# Ponte_h_-_Alternativa_2.net
KiCad netlist of a schematic drawn in EAGLE
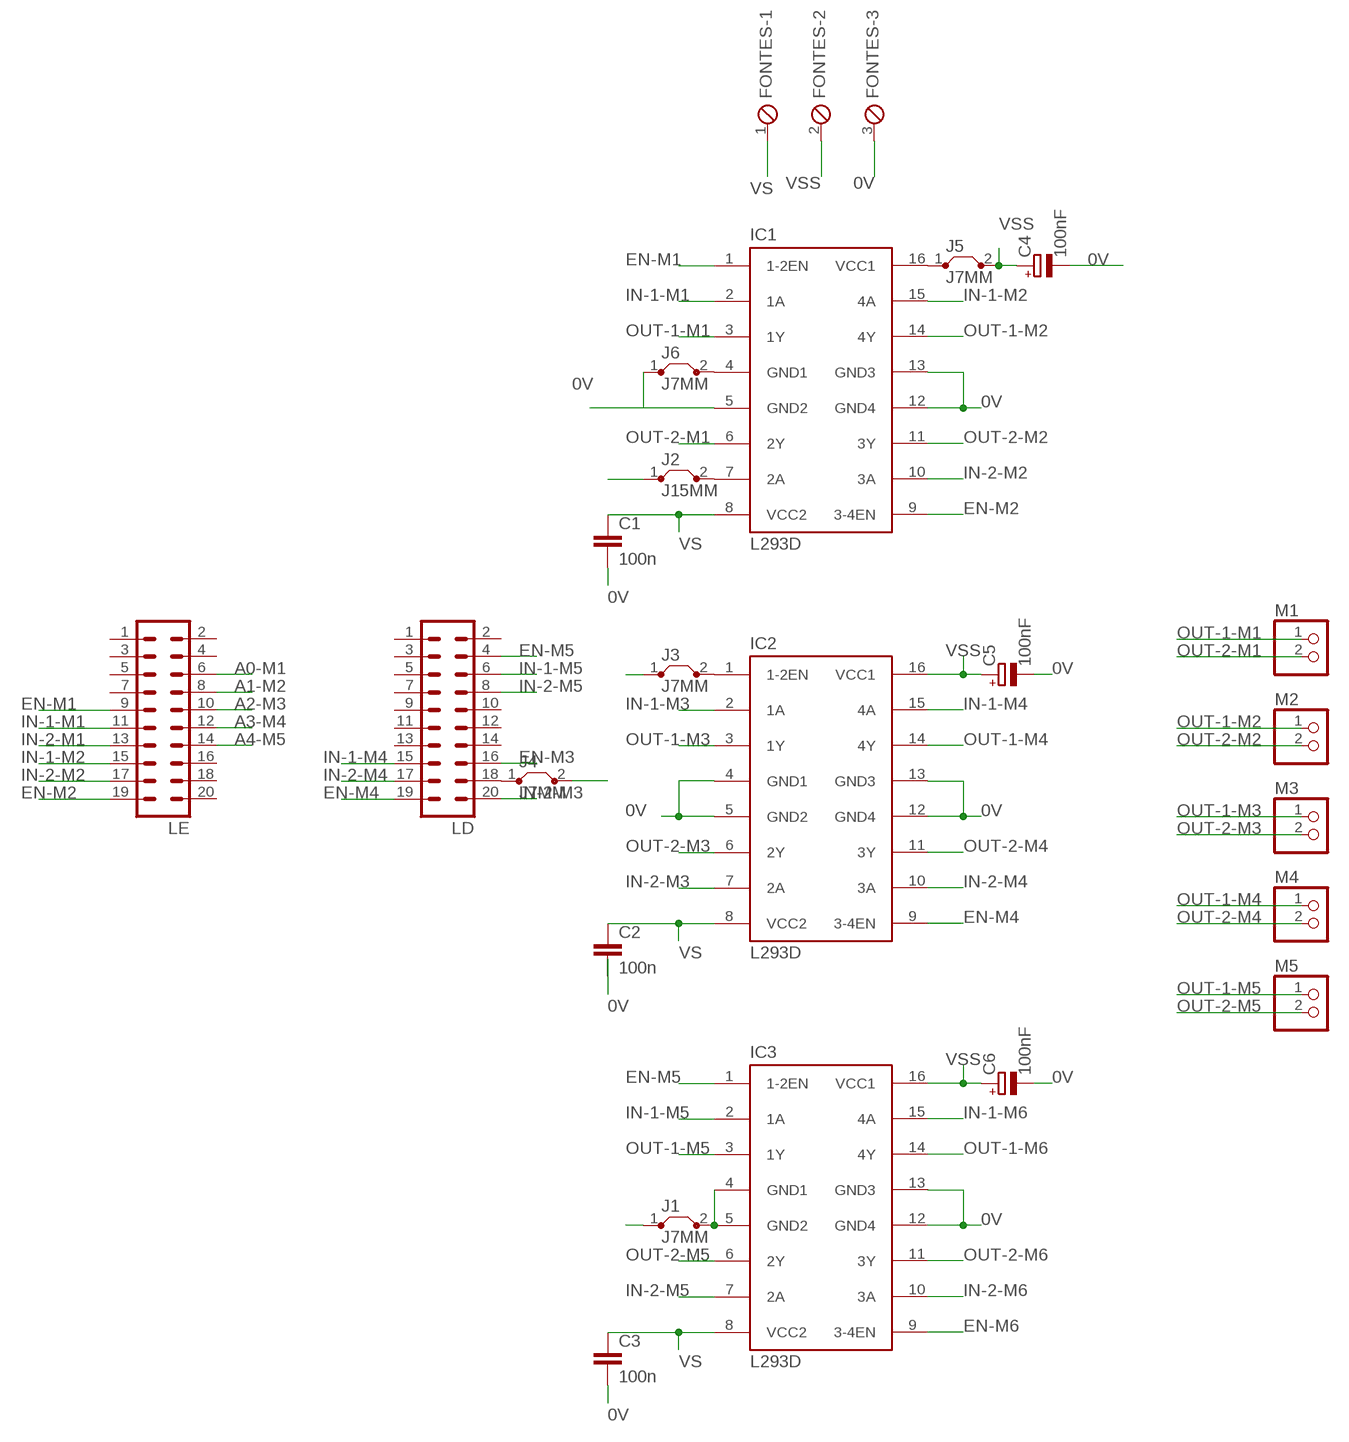
[diagram p0: schematic, sheet 1]

(export (version "E")
  (design (tool "Eeschema 10.0.6"))
  (components
    (comp (ref "C1")
      (value "100n")
      (footprint "eagle-import:C7.5B3")
      (libsource (lib "eagle-import") (part "C7.5/3"))
    )
    (comp (ref "C2")
      (value "100n")
      (footprint "eagle-import:C7.5B3")
      (libsource (lib "eagle-import") (part "C7.5/3"))
    )
    (comp (ref "C3")
      (value "100n")
      (footprint "eagle-import:C7.5B3")
      (libsource (lib "eagle-import") (part "C7.5/3"))
    )
    (comp (ref "C4")
      (value "100nF")
      (footprint "eagle-import:E1,8-4")
      (libsource (lib "eagle-import") (part "CPOL-EUE1.8-4"))
    )
    (comp (ref "C5")
      (value "100nF")
      (footprint "eagle-import:E1,8-4")
      (libsource (lib "eagle-import") (part "CPOL-EUE1.8-4"))
    )
    (comp (ref "C6")
      (value "100nF")
      (footprint "eagle-import:E1,8-4")
      (libsource (lib "eagle-import") (part "CPOL-EUE1.8-4"))
    )
    (comp (ref "FONTES")
      (value "MPT3")
      (footprint "eagle-import:3POL254")
      (libsource (lib "eagle-import") (part "MPT3"))
    )
    (comp (ref "IC1")
      (value "L293D")
      (footprint "eagle-import:DIL16")
      (libsource (lib "eagle-import") (part "L293D"))
    )
    (comp (ref "IC2")
      (value "L293D")
      (footprint "eagle-import:DIL16")
      (libsource (lib "eagle-import") (part "L293D"))
    )
    (comp (ref "IC3")
      (value "L293D")
      (footprint "eagle-import:DIL16")
      (libsource (lib "eagle-import") (part "L293D"))
    )
    (comp (ref "J1")
      (value "J7MM")
      (footprint "eagle-import:07")
      (libsource (lib "eagle-import") (part "J7MM"))
    )
    (comp (ref "J2")
      (value "J15MM")
      (footprint "eagle-import:15")
      (libsource (lib "eagle-import") (part "J15MM"))
    )
    (comp (ref "J3")
      (value "J7MM")
      (footprint "eagle-import:07")
      (libsource (lib "eagle-import") (part "J7MM"))
    )
    (comp (ref "J4")
      (value "J7MM")
      (footprint "eagle-import:07")
      (libsource (lib "eagle-import") (part "J7MM"))
    )
    (comp (ref "J5")
      (value "J7MM")
      (footprint "eagle-import:07")
      (libsource (lib "eagle-import") (part "J7MM"))
    )
    (comp (ref "J6")
      (value "J7MM")
      (footprint "eagle-import:07")
      (libsource (lib "eagle-import") (part "J7MM"))
    )
    (comp (ref "LD")
      (value "MA10-2")
      (footprint "eagle-import:MA10-2")
      (libsource (lib "eagle-import") (part "MA10-2"))
    )
    (comp (ref "LE")
      (value "MA10-2")
      (footprint "eagle-import:MA10-2")
      (libsource (lib "eagle-import") (part "MA10-2"))
    )
    (comp (ref "M1")
      (value "PINHD-1X2")
      (footprint "eagle-import:1X02")
      (libsource (lib "eagle-import") (part "PINHD-1X2"))
    )
    (comp (ref "M2")
      (value "PINHD-1X2")
      (footprint "eagle-import:1X02")
      (libsource (lib "eagle-import") (part "PINHD-1X2"))
    )
    (comp (ref "M3")
      (value "PINHD-1X2")
      (footprint "eagle-import:1X02")
      (libsource (lib "eagle-import") (part "PINHD-1X2"))
    )
    (comp (ref "M4")
      (value "PINHD-1X2")
      (footprint "eagle-import:1X02")
      (libsource (lib "eagle-import") (part "PINHD-1X2"))
    )
    (comp (ref "M5")
      (value "PINHD-1X2")
      (footprint "eagle-import:1X02")
      (libsource (lib "eagle-import") (part "PINHD-1X2"))
    )
  )
  (nets
    (net (code "1") (name "/0V") (class "Default")
      (node (ref "C1") (pin "2") (pinfunction "2_2") (pintype "passive"))
      (node (ref "C2") (pin "2") (pinfunction "2_2") (pintype "passive"))
      (node (ref "C3") (pin "2") (pinfunction "2_2") (pintype "passive"))
      (node (ref "C4") (pin "-") (pinfunction "-_-") (pintype "passive"))
      (node (ref "C5") (pin "-") (pinfunction "-_-") (pintype "passive"))
      (node (ref "C6") (pin "-") (pinfunction "-_-") (pintype "passive"))
      (node (ref "FONTES") (pin "3") (pinfunction "1_3") (pintype "passive"))
      (node (ref "IC1") (pin "12") (pinfunction "GND4_12") (pintype "power_in"))
      (node (ref "IC1") (pin "13") (pinfunction "GND3_13") (pintype "power_in"))
      (node (ref "IC1") (pin "5") (pinfunction "GND2_5") (pintype "power_in"))
      (node (ref "IC2") (pin "12") (pinfunction "GND4_12") (pintype "power_in"))
      (node (ref "IC2") (pin "13") (pinfunction "GND3_13") (pintype "power_in"))
      (node (ref "IC2") (pin "4") (pinfunction "GND1_4") (pintype "power_in"))
      (node (ref "IC2") (pin "5") (pinfunction "GND2_5") (pintype "power_in"))
      (node (ref "IC3") (pin "12") (pinfunction "GND4_12") (pintype "power_in"))
      (node (ref "IC3") (pin "13") (pinfunction "GND3_13") (pintype "power_in"))
      (node (ref "J1") (pin "1") (pinfunction "1_1") (pintype "passive"))
      (node (ref "J6") (pin "1") (pinfunction "1_1") (pintype "passive"))
    )
    (net (code "2") (name "/A0-M1") (class "Default")
      (node (ref "LE") (pin "6") (pinfunction "6_6") (pintype "passive"))
    )
    (net (code "3") (name "/A1-M2") (class "Default")
      (node (ref "LE") (pin "8") (pinfunction "8_8") (pintype "passive"))
    )
    (net (code "4") (name "/A2-M3") (class "Default")
      (node (ref "LE") (pin "10") (pinfunction "10_10") (pintype "passive"))
    )
    (net (code "5") (name "/A3-M4") (class "Default")
      (node (ref "LE") (pin "12") (pinfunction "12_12") (pintype "passive"))
    )
    (net (code "6") (name "/A4-M5") (class "Default")
      (node (ref "LE") (pin "14") (pinfunction "14_14") (pintype "passive"))
    )
    (net (code "7") (name "/EN-M1") (class "Default")
      (node (ref "IC1") (pin "1") (pinfunction "1-2EN_1") (pintype "input"))
      (node (ref "LE") (pin "9") (pinfunction "9_9") (pintype "passive"))
    )
    (net (code "8") (name "/EN-M2") (class "Default")
      (node (ref "IC1") (pin "9") (pinfunction "3-4EN_9") (pintype "input"))
      (node (ref "LE") (pin "19") (pinfunction "19_19") (pintype "passive"))
    )
    (net (code "9") (name "/EN-M3") (class "Default")
      (node (ref "J3") (pin "1") (pinfunction "1_1") (pintype "passive"))
      (node (ref "J4") (pin "2") (pinfunction "2_2") (pintype "passive"))
      (node (ref "LD") (pin "16") (pinfunction "16_16") (pintype "passive"))
    )
    (net (code "10") (name "/EN-M4") (class "Default")
      (node (ref "IC2") (pin "9") (pinfunction "3-4EN_9") (pintype "input"))
      (node (ref "LD") (pin "19") (pinfunction "19_19") (pintype "passive"))
    )
    (net (code "11") (name "/EN-M5") (class "Default")
      (node (ref "IC3") (pin "1") (pinfunction "1-2EN_1") (pintype "input"))
      (node (ref "LD") (pin "4") (pinfunction "4_4") (pintype "passive"))
    )
    (net (code "12") (name "/EN-M6") (class "Default")
      (node (ref "IC3") (pin "9") (pinfunction "3-4EN_9") (pintype "input"))
    )
    (net (code "13") (name "/IN-1-M1") (class "Default")
      (node (ref "IC1") (pin "2") (pinfunction "1A_2") (pintype "input"))
      (node (ref "LE") (pin "11") (pinfunction "11_11") (pintype "passive"))
    )
    (net (code "14") (name "/IN-1-M2") (class "Default")
      (node (ref "IC1") (pin "15") (pinfunction "4A_15") (pintype "input"))
      (node (ref "LE") (pin "15") (pinfunction "15_15") (pintype "passive"))
    )
    (net (code "15") (name "/IN-1-M3") (class "Default")
      (node (ref "IC2") (pin "2") (pinfunction "1A_2") (pintype "input"))
    )
    (net (code "16") (name "/IN-1-M4") (class "Default")
      (node (ref "IC2") (pin "15") (pinfunction "4A_15") (pintype "input"))
      (node (ref "LD") (pin "15") (pinfunction "15_15") (pintype "passive"))
    )
    (net (code "17") (name "/IN-1-M5") (class "Default")
      (node (ref "IC3") (pin "2") (pinfunction "1A_2") (pintype "input"))
      (node (ref "LD") (pin "6") (pinfunction "6_6") (pintype "passive"))
    )
    (net (code "18") (name "/IN-1-M6") (class "Default")
      (node (ref "IC3") (pin "15") (pinfunction "4A_15") (pintype "input"))
    )
    (net (code "19") (name "/IN-2-M1") (class "Default")
      (node (ref "J2") (pin "1") (pinfunction "1_1") (pintype "passive"))
      (node (ref "LE") (pin "13") (pinfunction "13_13") (pintype "passive"))
    )
    (net (code "20") (name "/IN-2-M2") (class "Default")
      (node (ref "IC1") (pin "10") (pinfunction "3A_10") (pintype "input"))
      (node (ref "LE") (pin "17") (pinfunction "17_17") (pintype "passive"))
    )
    (net (code "21") (name "/IN-2-M3") (class "Default")
      (node (ref "IC2") (pin "7") (pinfunction "2A_7") (pintype "input"))
      (node (ref "LD") (pin "20") (pinfunction "20_20") (pintype "passive"))
    )
    (net (code "22") (name "/IN-2-M4") (class "Default")
      (node (ref "IC2") (pin "10") (pinfunction "3A_10") (pintype "input"))
      (node (ref "LD") (pin "17") (pinfunction "17_17") (pintype "passive"))
    )
    (net (code "23") (name "/IN-2-M5") (class "Default")
      (node (ref "IC3") (pin "7") (pinfunction "2A_7") (pintype "input"))
      (node (ref "LD") (pin "8") (pinfunction "8_8") (pintype "passive"))
    )
    (net (code "24") (name "/IN-2-M6") (class "Default")
      (node (ref "IC3") (pin "10") (pinfunction "3A_10") (pintype "input"))
    )
    (net (code "25") (name "/OUT-1-M1") (class "Default")
      (node (ref "IC1") (pin "3") (pinfunction "1Y_3") (pintype "output"))
      (node (ref "M1") (pin "1") (pinfunction "1_1") (pintype "passive"))
    )
    (net (code "26") (name "/OUT-1-M2") (class "Default")
      (node (ref "IC1") (pin "14") (pinfunction "4Y_14") (pintype "output"))
      (node (ref "M2") (pin "1") (pinfunction "1_1") (pintype "passive"))
    )
    (net (code "27") (name "/OUT-1-M3") (class "Default")
      (node (ref "IC2") (pin "3") (pinfunction "1Y_3") (pintype "output"))
      (node (ref "M3") (pin "1") (pinfunction "1_1") (pintype "passive"))
    )
    (net (code "28") (name "/OUT-1-M4") (class "Default")
      (node (ref "IC2") (pin "14") (pinfunction "4Y_14") (pintype "output"))
      (node (ref "M4") (pin "1") (pinfunction "1_1") (pintype "passive"))
    )
    (net (code "29") (name "/OUT-1-M5") (class "Default")
      (node (ref "IC3") (pin "3") (pinfunction "1Y_3") (pintype "output"))
      (node (ref "M5") (pin "1") (pinfunction "1_1") (pintype "passive"))
    )
    (net (code "30") (name "/OUT-1-M6") (class "Default")
      (node (ref "IC3") (pin "14") (pinfunction "4Y_14") (pintype "output"))
    )
    (net (code "31") (name "/OUT-2-M1") (class "Default")
      (node (ref "IC1") (pin "6") (pinfunction "2Y_6") (pintype "output"))
      (node (ref "M1") (pin "2") (pinfunction "2_2") (pintype "passive"))
    )
    (net (code "32") (name "/OUT-2-M2") (class "Default")
      (node (ref "IC1") (pin "11") (pinfunction "3Y_11") (pintype "output"))
      (node (ref "M2") (pin "2") (pinfunction "2_2") (pintype "passive"))
    )
    (net (code "33") (name "/OUT-2-M3") (class "Default")
      (node (ref "IC2") (pin "6") (pinfunction "2Y_6") (pintype "output"))
      (node (ref "M3") (pin "2") (pinfunction "2_2") (pintype "passive"))
    )
    (net (code "34") (name "/OUT-2-M4") (class "Default")
      (node (ref "IC2") (pin "11") (pinfunction "3Y_11") (pintype "output"))
      (node (ref "M4") (pin "2") (pinfunction "2_2") (pintype "passive"))
    )
    (net (code "35") (name "/OUT-2-M5") (class "Default")
      (node (ref "IC3") (pin "6") (pinfunction "2Y_6") (pintype "output"))
      (node (ref "M5") (pin "2") (pinfunction "2_2") (pintype "passive"))
    )
    (net (code "36") (name "/OUT-2-M6") (class "Default")
      (node (ref "IC3") (pin "11") (pinfunction "3Y_11") (pintype "output"))
    )
    (net (code "37") (name "/VS") (class "Default")
      (node (ref "C1") (pin "1") (pinfunction "1_1") (pintype "passive"))
      (node (ref "C2") (pin "1") (pinfunction "1_1") (pintype "passive"))
      (node (ref "C3") (pin "1") (pinfunction "1_1") (pintype "passive"))
      (node (ref "FONTES") (pin "1") (pinfunction "1_1") (pintype "passive"))
      (node (ref "IC1") (pin "8") (pinfunction "VCC2_8") (pintype "power_in"))
      (node (ref "IC2") (pin "8") (pinfunction "VCC2_8") (pintype "power_in"))
      (node (ref "IC3") (pin "8") (pinfunction "VCC2_8") (pintype "power_in"))
    )
    (net (code "38") (name "/VSS") (class "Default")
      (node (ref "C4") (pin "+") (pinfunction "+_+") (pintype "passive"))
      (node (ref "C5") (pin "+") (pinfunction "+_+") (pintype "passive"))
      (node (ref "C6") (pin "+") (pinfunction "+_+") (pintype "passive"))
      (node (ref "FONTES") (pin "2") (pinfunction "1_2") (pintype "passive"))
      (node (ref "IC2") (pin "16") (pinfunction "VCC1_16") (pintype "power_in"))
      (node (ref "IC3") (pin "16") (pinfunction "VCC1_16") (pintype "power_in"))
      (node (ref "J5") (pin "2") (pinfunction "2_2") (pintype "passive"))
    )
    (net (code "39") (name "Net-(IC1-2A)") (class "Default")
      (node (ref "IC1") (pin "7") (pinfunction "2A_7") (pintype "input"))
      (node (ref "J2") (pin "2") (pinfunction "2_2") (pintype "passive"))
    )
    (net (code "40") (name "Net-(IC1-GND1)") (class "Default")
      (node (ref "IC1") (pin "4") (pinfunction "GND1_4") (pintype "power_in"))
      (node (ref "J6") (pin "2") (pinfunction "2_2") (pintype "passive"))
    )
    (net (code "41") (name "Net-(IC1-VCC1)") (class "Default")
      (node (ref "IC1") (pin "16") (pinfunction "VCC1_16") (pintype "power_in"))
      (node (ref "J5") (pin "1") (pinfunction "1_1") (pintype "passive"))
    )
    (net (code "42") (name "Net-(IC2-1-2EN)") (class "Default")
      (node (ref "IC2") (pin "1") (pinfunction "1-2EN_1") (pintype "input"))
      (node (ref "J3") (pin "2") (pinfunction "2_2") (pintype "passive"))
    )
    (net (code "43") (name "Net-(IC3-GND1)") (class "Default")
      (node (ref "IC3") (pin "4") (pinfunction "GND1_4") (pintype "power_in"))
      (node (ref "IC3") (pin "5") (pinfunction "GND2_5") (pintype "power_in"))
      (node (ref "J1") (pin "2") (pinfunction "2_2") (pintype "passive"))
    )
    (net (code "44") (name "Net-(J4-Pad1)") (class "Default")
      (node (ref "J4") (pin "1") (pinfunction "1_1") (pintype "passive"))
      (node (ref "LD") (pin "18") (pinfunction "18_18") (pintype "passive"))
    )
    (net (code "45") (name "unconnected-(LD-Pad1)") (class "Default")
      (node (ref "LD") (pin "1") (pinfunction "1_1") (pintype "passive"))
    )
    (net (code "46") (name "unconnected-(LD-Pad2)") (class "Default")
      (node (ref "LD") (pin "2") (pinfunction "2_2") (pintype "passive"))
    )
    (net (code "47") (name "unconnected-(LD-Pad3)") (class "Default")
      (node (ref "LD") (pin "3") (pinfunction "3_3") (pintype "passive"))
    )
    (net (code "48") (name "unconnected-(LD-Pad5)") (class "Default")
      (node (ref "LD") (pin "5") (pinfunction "5_5") (pintype "passive"))
    )
    (net (code "49") (name "unconnected-(LD-Pad7)") (class "Default")
      (node (ref "LD") (pin "7") (pinfunction "7_7") (pintype "passive"))
    )
    (net (code "50") (name "unconnected-(LD-Pad9)") (class "Default")
      (node (ref "LD") (pin "9") (pinfunction "9_9") (pintype "passive"))
    )
    (net (code "51") (name "unconnected-(LD-Pad10)") (class "Default")
      (node (ref "LD") (pin "10") (pinfunction "10_10") (pintype "passive"))
    )
    (net (code "52") (name "unconnected-(LD-Pad11)") (class "Default")
      (node (ref "LD") (pin "11") (pinfunction "11_11") (pintype "passive"))
    )
    (net (code "53") (name "unconnected-(LD-Pad12)") (class "Default")
      (node (ref "LD") (pin "12") (pinfunction "12_12") (pintype "passive"))
    )
    (net (code "54") (name "unconnected-(LD-Pad13)") (class "Default")
      (node (ref "LD") (pin "13") (pinfunction "13_13") (pintype "passive"))
    )
    (net (code "55") (name "unconnected-(LD-Pad14)") (class "Default")
      (node (ref "LD") (pin "14") (pinfunction "14_14") (pintype "passive"))
    )
    (net (code "56") (name "unconnected-(LE-Pad1)") (class "Default")
      (node (ref "LE") (pin "1") (pinfunction "1_1") (pintype "passive"))
    )
    (net (code "57") (name "unconnected-(LE-Pad2)") (class "Default")
      (node (ref "LE") (pin "2") (pinfunction "2_2") (pintype "passive"))
    )
    (net (code "58") (name "unconnected-(LE-Pad3)") (class "Default")
      (node (ref "LE") (pin "3") (pinfunction "3_3") (pintype "passive"))
    )
    (net (code "59") (name "unconnected-(LE-Pad4)") (class "Default")
      (node (ref "LE") (pin "4") (pinfunction "4_4") (pintype "passive"))
    )
    (net (code "60") (name "unconnected-(LE-Pad5)") (class "Default")
      (node (ref "LE") (pin "5") (pinfunction "5_5") (pintype "passive"))
    )
    (net (code "61") (name "unconnected-(LE-Pad7)") (class "Default")
      (node (ref "LE") (pin "7") (pinfunction "7_7") (pintype "passive"))
    )
    (net (code "62") (name "unconnected-(LE-Pad16)") (class "Default")
      (node (ref "LE") (pin "16") (pinfunction "16_16") (pintype "passive"))
    )
    (net (code "63") (name "unconnected-(LE-Pad18)") (class "Default")
      (node (ref "LE") (pin "18") (pinfunction "18_18") (pintype "passive"))
    )
    (net (code "64") (name "unconnected-(LE-Pad20)") (class "Default")
      (node (ref "LE") (pin "20") (pinfunction "20_20") (pintype "passive"))
    )
  )
)
